# quadcopter.net
KiCad netlist of a schematic drawn in EAGLE
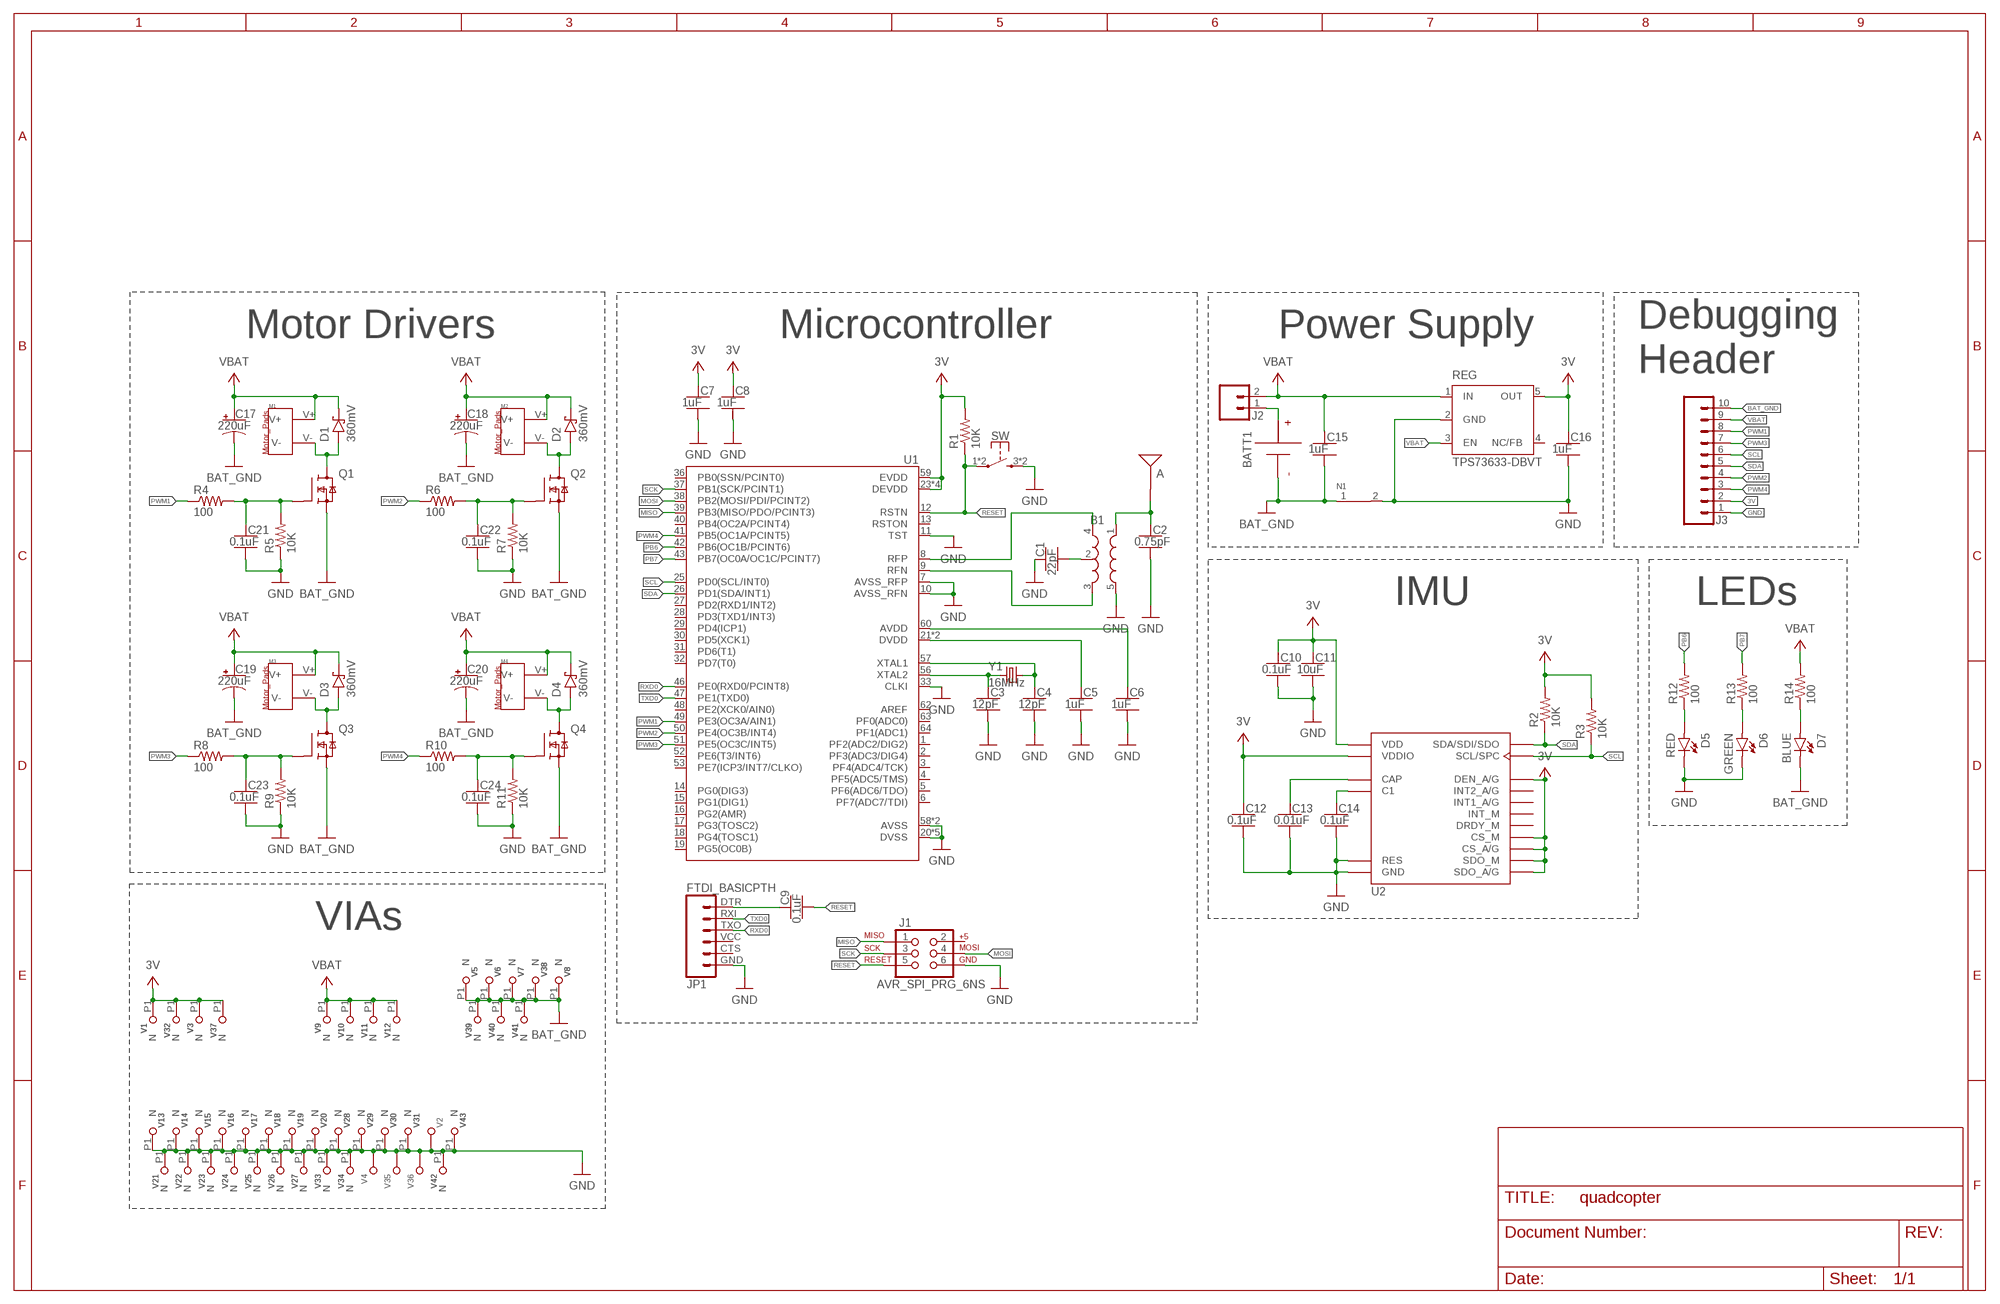
[diagram p0: schematic, sheet 1]

(export (version "E")
  (design (tool "Eeschema 10.0.6"))
  (components
    (comp (ref "A")
      (value "ANTENNA2SMD5")
      (footprint "eagle-import:ANTENNA-CHIP5")
      (fields (field (name "MFR") "Linx Technologies Inc.") (field (name "MPN") "ANT-2.45-CHP-T"))
      (libsource (lib "eagle-import") (part "ANTENNA2SMD5"))
    )
    (comp (ref "B1")
      (value "BALUN0805")
      (footprint "eagle-import:BALUN")
      (fields (field (name "MFR") "Wurth Electronics Inc") (field (name "MPN") "748421245"))
      (libsource (lib "eagle-import") (part "BALUN0805"))
    )
    (comp (ref "BATT1")
      (value "BATTERY")
      (footprint "eagle-import:BATTERY-TERMINALS")
      (libsource (lib "eagle-import") (part "BATTERY"))
    )
    (comp (ref "C1")
      (value "22pF")
      (footprint "eagle-import:CAPC2012X140_HS")
      (fields
        (field (name "MFR") "Murata Electronics North America")
        (field (name "MPN") "GRM21A5C2E220JW01D")
      )
      (libsource (lib "eagle-import") (part "CAPACITOR-NP_SMD-2012-0805_CERAMIC-22PF"))
    )
    (comp (ref "C2")
      (value "0.75pF")
      (footprint "eagle-import:CAPC2012X140_HS")
      (fields
        (field (name "MFR") "Murata Electronics North America")
        (field (name "MPN") "GQM2195C2AR75CB01D")
      )
      (libsource (lib "eagle-import") (part "CAPACITOR-NP_SMD-2012-0805_CERAMIC-0.75PF"))
    )
    (comp (ref "C3")
      (value "12pF")
      (footprint "eagle-import:CAPC2012X140_HS")
      (fields
        (field (name "MFR") "Murata Electronics North America")
        (field (name "MPN") "GRM21A5C2E120JW01D")
      )
      (libsource (lib "eagle-import") (part "CAPACITOR-NP_SMD-2012-0805_CERAMIC-12PF"))
    )
    (comp (ref "C4")
      (value "12pF")
      (footprint "eagle-import:CAPC2012X140_HS")
      (fields
        (field (name "MFR") "Murata Electronics North America")
        (field (name "MPN") "GRM21A5C2E120JW01D")
      )
      (libsource (lib "eagle-import") (part "CAPACITOR-NP_SMD-2012-0805_CERAMIC-12PF"))
    )
    (comp (ref "C5")
      (value "1uF")
      (footprint "eagle-import:CAPC2012X140_HS")
      (fields (field (name "MFR") "Taiyo Yuden") (field (name "MPN") "TMK212B7105KG-T"))
      (libsource (lib "eagle-import") (part "CAPACITOR-NP_SMD-2012-0805_CERAMIC-1UF"))
    )
    (comp (ref "C6")
      (value "1uF")
      (footprint "eagle-import:CAPC2012X140_HS")
      (fields (field (name "MFR") "Taiyo Yuden") (field (name "MPN") "TMK212B7105KG-T"))
      (libsource (lib "eagle-import") (part "CAPACITOR-NP_SMD-2012-0805_CERAMIC-1UF"))
    )
    (comp (ref "C7")
      (value "1uF")
      (footprint "eagle-import:CAPC2012X140_HS")
      (fields (field (name "MFR") "Taiyo Yuden") (field (name "MPN") "TMK212B7105KG-T"))
      (libsource (lib "eagle-import") (part "CAPACITOR-NP_SMD-2012-0805_CERAMIC-1UF"))
    )
    (comp (ref "C8")
      (value "1uF")
      (footprint "eagle-import:CAPC2012X140_HS")
      (fields (field (name "MFR") "Taiyo Yuden") (field (name "MPN") "TMK212B7105KG-T"))
      (libsource (lib "eagle-import") (part "CAPACITOR-NP_SMD-2012-0805_CERAMIC-1UF"))
    )
    (comp (ref "C9")
      (value "0.1uF")
      (footprint "eagle-import:CAPC2012X140_HS")
      (fields (field (name "MFR") "TDK") (field (name "MPN") "C2012X7R2A104K125AA"))
      (libsource (lib "eagle-import") (part "CAPACITOR-NP_SMD-2012-0805_CERAMIC-0.1UF"))
    )
    (comp (ref "C10")
      (value "0.1uF")
      (footprint "eagle-import:CAPC2012X140_HS")
      (fields (field (name "MFR") "TDK") (field (name "MPN") "C2012X7R2A104K125AA"))
      (libsource (lib "eagle-import") (part "CAPACITOR-NP_SMD-2012-0805_CERAMIC-0.1UF"))
    )
    (comp (ref "C11")
      (value "10uF")
      (footprint "eagle-import:CAPC2012X140_HS")
      (fields (field (name "MFR") "TDK Corporation") (field (name "MPN") "C2012X5R1E106M085AC"))
      (libsource (lib "eagle-import") (part "CAPACITOR-NP_SMD-2012-0805_CERAMIC-10UF"))
    )
    (comp (ref "C12")
      (value "0.1uF")
      (footprint "eagle-import:CAPC2012X140_HS")
      (fields (field (name "MFR") "TDK") (field (name "MPN") "C2012X7R2A104K125AA"))
      (libsource (lib "eagle-import") (part "CAPACITOR-NP_SMD-2012-0805_CERAMIC-0.1UF"))
    )
    (comp (ref "C13")
      (value "0.01uF")
      (footprint "eagle-import:CAPC2012X140_HS")
      (fields (field (name "MFR") "Knowles Syfer") (field (name "MPN") "0805J0500104KJT"))
      (libsource (lib "eagle-import") (part "CAPACITOR-NP_SMD-2012-0805_CERAMIC-0.01UF"))
    )
    (comp (ref "C14")
      (value "0.1uF")
      (footprint "eagle-import:CAPC2012X140_HS")
      (fields (field (name "MFR") "TDK") (field (name "MPN") "C2012X7R2A104K125AA"))
      (libsource (lib "eagle-import") (part "CAPACITOR-NP_SMD-2012-0805_CERAMIC-0.1UF"))
    )
    (comp (ref "C15")
      (value "1uF")
      (footprint "eagle-import:CAPC2012X140_HS")
      (fields (field (name "MFR") "Taiyo Yuden") (field (name "MPN") "TMK212B7105KG-T"))
      (libsource (lib "eagle-import") (part "CAPACITOR-NP_SMD-2012-0805_CERAMIC-1UF"))
    )
    (comp (ref "C16")
      (value "1uF")
      (footprint "eagle-import:CAPC2012X140_HS")
      (fields (field (name "MFR") "Taiyo Yuden") (field (name "MPN") "TMK212B7105KG-T"))
      (libsource (lib "eagle-import") (part "CAPACITOR-NP_SMD-2012-0805_CERAMIC-1UF"))
    )
    (comp (ref "C17")
      (value "220uF")
      (footprint "eagle-import:CAPMP7343X310_HS")
      (fields (field (name "MFR") "AVX Corporation") (field (name "MPN") "TAJD227K006RNJ"))
      (libsource (lib "eagle-import") (part "CAPACITOR-POL_SMD-7043-D_TANTALUM-220UF"))
    )
    (comp (ref "C18")
      (value "220uF")
      (footprint "eagle-import:CAPMP7343X310_HS")
      (fields (field (name "MFR") "AVX Corporation") (field (name "MPN") "TAJD227K006RNJ"))
      (libsource (lib "eagle-import") (part "CAPACITOR-POL_SMD-7043-D_TANTALUM-220UF"))
    )
    (comp (ref "C19")
      (value "220uF")
      (footprint "eagle-import:CAPMP7343X310_HS")
      (fields (field (name "MFR") "AVX Corporation") (field (name "MPN") "TAJD227K006RNJ"))
      (libsource (lib "eagle-import") (part "CAPACITOR-POL_SMD-7043-D_TANTALUM-220UF"))
    )
    (comp (ref "C20")
      (value "220uF")
      (footprint "eagle-import:CAPMP7343X310_HS")
      (fields (field (name "MFR") "AVX Corporation") (field (name "MPN") "TAJD227K006RNJ"))
      (libsource (lib "eagle-import") (part "CAPACITOR-POL_SMD-7043-D_TANTALUM-220UF"))
    )
    (comp (ref "C21")
      (value "0.1uF")
      (footprint "eagle-import:CAPC2012X140_HS")
      (fields (field (name "MFR") "TDK") (field (name "MPN") "C2012X7R2A104K125AA"))
      (libsource (lib "eagle-import") (part "CAPACITOR-NP_SMD-2012-0805_CERAMIC-0.1UF"))
    )
    (comp (ref "C22")
      (value "0.1uF")
      (footprint "eagle-import:CAPC2012X140_HS")
      (fields (field (name "MFR") "TDK") (field (name "MPN") "C2012X7R2A104K125AA"))
      (libsource (lib "eagle-import") (part "CAPACITOR-NP_SMD-2012-0805_CERAMIC-0.1UF"))
    )
    (comp (ref "C23")
      (value "0.1uF")
      (footprint "eagle-import:CAPC2012X140_HS")
      (fields (field (name "MFR") "TDK") (field (name "MPN") "C2012X7R2A104K125AA"))
      (libsource (lib "eagle-import") (part "CAPACITOR-NP_SMD-2012-0805_CERAMIC-0.1UF"))
    )
    (comp (ref "C24")
      (value "0.1uF")
      (footprint "eagle-import:CAPC2012X140_HS")
      (fields (field (name "MFR") "TDK") (field (name "MPN") "C2012X7R2A104K125AA"))
      (libsource (lib "eagle-import") (part "CAPACITOR-NP_SMD-2012-0805_CERAMIC-0.1UF"))
    )
    (comp (ref "D1")
      (value "360mV")
      (footprint "eagle-import:SOD3716X135_HS")
      (fields
        (field (name "MFR") "Toshiba Semiconductor and Storage")
        (field (name "MPN") "CRS08(TE85L,Q,M)")
      )
      (libsource (lib "eagle-import") (part "DIODE-SCHOTTKY_SMD-SOD123-360MV"))
    )
    (comp (ref "D2")
      (value "360mV")
      (footprint "eagle-import:SOD3716X135_HS")
      (fields
        (field (name "MFR") "Toshiba Semiconductor and Storage")
        (field (name "MPN") "CRS08(TE85L,Q,M)")
      )
      (libsource (lib "eagle-import") (part "DIODE-SCHOTTKY_SMD-SOD123-360MV"))
    )
    (comp (ref "D3")
      (value "360mV")
      (footprint "eagle-import:SOD3716X135_HS")
      (fields
        (field (name "MFR") "Toshiba Semiconductor and Storage")
        (field (name "MPN") "CRS08(TE85L,Q,M)")
      )
      (libsource (lib "eagle-import") (part "DIODE-SCHOTTKY_SMD-SOD123-360MV"))
    )
    (comp (ref "D4")
      (value "360mV")
      (footprint "eagle-import:SOD3716X135_HS")
      (fields
        (field (name "MFR") "Toshiba Semiconductor and Storage")
        (field (name "MPN") "CRS08(TE85L,Q,M)")
      )
      (libsource (lib "eagle-import") (part "DIODE-SCHOTTKY_SMD-SOD123-360MV"))
    )
    (comp (ref "D5")
      (value "RED")
      (footprint "eagle-import:LED_0805")
      (fields (field (name "MFR") "Lite-On Inc") (field (name "MPN") "LTST-C170KRKT"))
      (libsource (lib "eagle-import") (part "LED_RED"))
    )
    (comp (ref "D6")
      (value "GREEN")
      (footprint "eagle-import:LED_0805")
      (fields (field (name "MFR") "Lite-On Inc") (field (name "MPN") "LTST-C170TGKT"))
      (libsource (lib "eagle-import") (part "LED_GREEN"))
    )
    (comp (ref "D7")
      (value "BLUE")
      (footprint "eagle-import:LED_0805")
      (fields (field (name "MFR") "Lite-On Inc") (field (name "MPN") "LTST-C170TBKT"))
      (libsource (lib "eagle-import") (part "LED_BLUE"))
    )
    (comp (ref "J1")
      (value "AVR_SPI_PRG_6NS")
      (footprint "eagle-import:2X3-NS")
      (fields (field (name "MFR") "Amphenol FCI") (field (name "MPN") "67997-206HLF"))
      (libsource (lib "eagle-import") (part "AVR_SPI_PRG_6NS"))
    )
    (comp (ref "J2")
      (value "MALE_HEADER_2POS-2X1-0.1IN")
      (footprint "eagle-import:MALE_HEADER_2X1_0.1IN")
      (fields (field (name "MFR") "3M") (field (name "MPN") "961102-6404-AR"))
      (libsource (lib "eagle-import") (part "MALE_HEADER_2POS-2X1-0.1IN"))
    )
    (comp (ref "J3")
      (value "SIP-10_TH-254X10")
      (footprint "eagle-import:HDRV10W63P254_10X1_2540X254H838_HS")
      (fields (field (name "MFR") "Amphenol FCI") (field (name "MPN") "68000-110HLF"))
      (libsource (lib "eagle-import") (part "SIP-10_TH-254X10"))
    )
    (comp (ref "JP1")
      (value "FTDI_BASICPTH")
      (footprint "eagle-import:FTDI_BASIC")
      (fields (field (name "MFR") "Amphenol FCI") (field (name "MPN") "68016-406HLF"))
      (libsource (lib "eagle-import") (part "FTDI_BASICPTH"))
    )
    (comp (ref "M1")
      (value "MOTOR_PADS")
      (footprint "eagle-import:MOTOR_PADS")
      (fields (field (name "MFR") "NA"))
      (libsource (lib "eagle-import") (part "MOTOR_PADS"))
    )
    (comp (ref "M2")
      (value "MOTOR_PADS")
      (footprint "eagle-import:MOTOR_PADS")
      (fields (field (name "MFR") "NA"))
      (libsource (lib "eagle-import") (part "MOTOR_PADS"))
    )
    (comp (ref "M3")
      (value "MOTOR_PADS")
      (footprint "eagle-import:MOTOR_PADS")
      (fields (field (name "MFR") "NA"))
      (libsource (lib "eagle-import") (part "MOTOR_PADS"))
    )
    (comp (ref "M4")
      (value "MOTOR_PADS")
      (footprint "eagle-import:MOTOR_PADS")
      (fields (field (name "MFR") "NA"))
      (libsource (lib "eagle-import") (part "MOTOR_PADS"))
    )
    (comp (ref "N1")
      (value "NET_BRIDGE")
      (footprint "eagle-import:NET_BRIDGE")
      (libsource (lib "eagle-import") (part "NET_BRIDGE"))
    )
    (comp (ref "Q1")
      (value "MOSFET_SOT-23")
      (footprint "eagle-import:SI2302CDS_T1_E3")
      (fields (field (name "MFR") "Vishay Siliconix") (field (name "MPN") "SI2302CDS-T1-E3"))
      (libsource (lib "eagle-import") (part "MOSFET_SOT-23"))
    )
    (comp (ref "Q2")
      (value "MOSFET_SOT-23")
      (footprint "eagle-import:SI2302CDS_T1_E3")
      (fields (field (name "MFR") "Vishay Siliconix") (field (name "MPN") "SI2302CDS-T1-E3"))
      (libsource (lib "eagle-import") (part "MOSFET_SOT-23"))
    )
    (comp (ref "Q3")
      (value "MOSFET_SOT-23")
      (footprint "eagle-import:SI2302CDS_T1_E3")
      (fields (field (name "MFR") "Vishay Siliconix") (field (name "MPN") "SI2302CDS-T1-E3"))
      (libsource (lib "eagle-import") (part "MOSFET_SOT-23"))
    )
    (comp (ref "Q4")
      (value "MOSFET_SOT-23")
      (footprint "eagle-import:SI2302CDS_T1_E3")
      (fields (field (name "MFR") "Vishay Siliconix") (field (name "MPN") "SI2302CDS-T1-E3"))
      (libsource (lib "eagle-import") (part "MOSFET_SOT-23"))
    )
    (comp (ref "R1")
      (value "10K")
      (footprint "eagle-import:RESC2012X60_HS")
      (fields (field (name "MFR") "Yageo") (field (name "MPN") "RC0805JR-0710KL"))
      (libsource (lib "eagle-import") (part "RESISTOR_SMD-2012-0805-10K"))
    )
    (comp (ref "R2")
      (value "10K")
      (footprint "eagle-import:RESC2012X60_HS")
      (fields (field (name "MFR") "Yageo") (field (name "MPN") "RC0805JR-0710KL"))
      (libsource (lib "eagle-import") (part "RESISTOR_SMD-2012-0805-10K"))
    )
    (comp (ref "R3")
      (value "10K")
      (footprint "eagle-import:RESC2012X60_HS")
      (fields (field (name "MFR") "Yageo") (field (name "MPN") "RC0805JR-0710KL"))
      (libsource (lib "eagle-import") (part "RESISTOR_SMD-2012-0805-10K"))
    )
    (comp (ref "R4")
      (value "100")
      (footprint "eagle-import:RESC2012X60_HS")
      (fields (field (name "MFR") "Yageo") (field (name "MPN") "RC0805JR-07100RL"))
      (libsource (lib "eagle-import") (part "RESISTOR_SMD-2012-0805-100"))
    )
    (comp (ref "R5")
      (value "10K")
      (footprint "eagle-import:RESC2012X60_HS")
      (fields (field (name "MFR") "Yageo") (field (name "MPN") "RC0805JR-0710KL"))
      (libsource (lib "eagle-import") (part "RESISTOR_SMD-2012-0805-10K"))
    )
    (comp (ref "R6")
      (value "100")
      (footprint "eagle-import:RESC2012X60_HS")
      (fields (field (name "MFR") "Yageo") (field (name "MPN") "RC0805JR-07100RL"))
      (libsource (lib "eagle-import") (part "RESISTOR_SMD-2012-0805-100"))
    )
    (comp (ref "R7")
      (value "10K")
      (footprint "eagle-import:RESC2012X60_HS")
      (fields (field (name "MFR") "Yageo") (field (name "MPN") "RC0805JR-0710KL"))
      (libsource (lib "eagle-import") (part "RESISTOR_SMD-2012-0805-10K"))
    )
    (comp (ref "R8")
      (value "100")
      (footprint "eagle-import:RESC2012X60_HS")
      (fields (field (name "MFR") "Yageo") (field (name "MPN") "RC0805JR-07100RL"))
      (libsource (lib "eagle-import") (part "RESISTOR_SMD-2012-0805-100"))
    )
    (comp (ref "R9")
      (value "10K")
      (footprint "eagle-import:RESC2012X60_HS")
      (fields (field (name "MFR") "Yageo") (field (name "MPN") "RC0805JR-0710KL"))
      (libsource (lib "eagle-import") (part "RESISTOR_SMD-2012-0805-10K"))
    )
    (comp (ref "R10")
      (value "100")
      (footprint "eagle-import:RESC2012X60_HS")
      (fields (field (name "MFR") "Yageo") (field (name "MPN") "RC0805JR-07100RL"))
      (libsource (lib "eagle-import") (part "RESISTOR_SMD-2012-0805-100"))
    )
    (comp (ref "R11")
      (value "10K")
      (footprint "eagle-import:RESC2012X60_HS")
      (fields (field (name "MFR") "Yageo") (field (name "MPN") "RC0805JR-0710KL"))
      (libsource (lib "eagle-import") (part "RESISTOR_SMD-2012-0805-10K"))
    )
    (comp (ref "R12")
      (value "100")
      (footprint "eagle-import:RESC2012X60_HS")
      (fields (field (name "MFR") "Yageo") (field (name "MPN") "RC0805JR-07100RL"))
      (libsource (lib "eagle-import") (part "RESISTOR_SMD-2012-0805-100"))
    )
    (comp (ref "R13")
      (value "100")
      (footprint "eagle-import:RESC2012X60_HS")
      (fields (field (name "MFR") "Yageo") (field (name "MPN") "RC0805JR-07100RL"))
      (libsource (lib "eagle-import") (part "RESISTOR_SMD-2012-0805-100"))
    )
    (comp (ref "R14")
      (value "100")
      (footprint "eagle-import:RESC2012X60_HS")
      (fields (field (name "MFR") "Yageo") (field (name "MPN") "RC0805JR-07100RL"))
      (libsource (lib "eagle-import") (part "RESISTOR_SMD-2012-0805-100"))
    )
    (comp (ref "REG")
      (value "TPS73633-DBVT")
      (footprint "eagle-import:SOT23-DBV")
      (fields (field (name "MFR") "Texas Instruments") (field (name "MPN") "LP3985IM5X-3.0/NOPB"))
      (libsource (lib "eagle-import") (part "TPS73633-DBVT"))
    )
    (comp (ref "SW")
      (value "PUSHBUTTON_SMD-VERTICAL-1")
      (footprint "eagle-import:TE_FSM8JSMA_HS")
      (fields (field (name "MFR") "TE Connectivity Alcoswitch Switches") (field (name "MPN") "FSM4JSMA"))
      (libsource (lib "eagle-import") (part "PUSHBUTTON_SMD-VERTICAL-1"))
    )
    (comp (ref "U1")
      (value "ATMEGA128RFA1")
      (footprint "eagle-import:QFN-64")
      (fields (field (name "MFR") "Atmel") (field (name "MPN") "ATMEGA128RFA1-ZUR00"))
      (libsource (lib "eagle-import") (part "ATMEGA128RFA1"))
    )
    (comp (ref "U2")
      (value "IMU_LSM9DS1TR")
      (footprint "eagle-import:LSM9DS1TR")
      (fields (field (name "MFR") "STMicroelectronics") (field (name "MPN") "LSM9DS1TR"))
      (libsource (lib "eagle-import") (part "IMU_LSM9DS1TR"))
    )
    (comp (ref "V1")
      (value "LOCKED-VIA-0.254")
      (footprint "eagle-import:VIA-0.254MM")
      (libsource (lib "eagle-import") (part "LOCKED-VIA-0.254"))
    )
    (comp (ref "V2")
      (value "VIA_0.454")
      (footprint "eagle-import:VIA_0.454")
      (libsource (lib "eagle-import") (part "VIA_0.454"))
    )
    (comp (ref "V3")
      (value "LOCKED-VIA-0.254")
      (footprint "eagle-import:VIA-0.254MM")
      (libsource (lib "eagle-import") (part "LOCKED-VIA-0.254"))
    )
    (comp (ref "V4")
      (value "VIA_0.454")
      (footprint "eagle-import:VIA_0.454")
      (libsource (lib "eagle-import") (part "VIA_0.454"))
    )
    (comp (ref "V5")
      (value "LOCKED-VIA-0.254")
      (footprint "eagle-import:VIA-0.254MM")
      (libsource (lib "eagle-import") (part "LOCKED-VIA-0.254"))
    )
    (comp (ref "V6")
      (value "LOCKED-VIA-0.254")
      (footprint "eagle-import:VIA-0.254MM")
      (libsource (lib "eagle-import") (part "LOCKED-VIA-0.254"))
    )
    (comp (ref "V7")
      (value "LOCKED-VIA-0.254")
      (footprint "eagle-import:VIA-0.254MM")
      (libsource (lib "eagle-import") (part "LOCKED-VIA-0.254"))
    )
    (comp (ref "V8")
      (value "LOCKED-VIA-0.254")
      (footprint "eagle-import:VIA-0.254MM")
      (libsource (lib "eagle-import") (part "LOCKED-VIA-0.254"))
    )
    (comp (ref "V9")
      (value "LOCKED-VIA-0.254")
      (footprint "eagle-import:VIA-0.254MM")
      (libsource (lib "eagle-import") (part "LOCKED-VIA-0.254"))
    )
    (comp (ref "V10")
      (value "LOCKED-VIA-0.254")
      (footprint "eagle-import:VIA-0.254MM")
      (libsource (lib "eagle-import") (part "LOCKED-VIA-0.254"))
    )
    (comp (ref "V11")
      (value "LOCKED-VIA-0.254")
      (footprint "eagle-import:VIA-0.254MM")
      (libsource (lib "eagle-import") (part "LOCKED-VIA-0.254"))
    )
    (comp (ref "V12")
      (value "LOCKED-VIA-0.254")
      (footprint "eagle-import:VIA-0.254MM")
      (libsource (lib "eagle-import") (part "LOCKED-VIA-0.254"))
    )
    (comp (ref "V13")
      (value "LOCKED-VIA-0.254")
      (footprint "eagle-import:VIA-0.254MM")
      (libsource (lib "eagle-import") (part "LOCKED-VIA-0.254"))
    )
    (comp (ref "V14")
      (value "LOCKED-VIA-0.254")
      (footprint "eagle-import:VIA-0.254MM")
      (libsource (lib "eagle-import") (part "LOCKED-VIA-0.254"))
    )
    (comp (ref "V15")
      (value "LOCKED-VIA-0.254")
      (footprint "eagle-import:VIA-0.254MM")
      (libsource (lib "eagle-import") (part "LOCKED-VIA-0.254"))
    )
    (comp (ref "V16")
      (value "LOCKED-VIA-0.254")
      (footprint "eagle-import:VIA-0.254MM")
      (libsource (lib "eagle-import") (part "LOCKED-VIA-0.254"))
    )
    (comp (ref "V17")
      (value "LOCKED-VIA-0.254")
      (footprint "eagle-import:VIA-0.254MM")
      (libsource (lib "eagle-import") (part "LOCKED-VIA-0.254"))
    )
    (comp (ref "V18")
      (value "LOCKED-VIA-0.254")
      (footprint "eagle-import:VIA-0.254MM")
      (libsource (lib "eagle-import") (part "LOCKED-VIA-0.254"))
    )
    (comp (ref "V19")
      (value "LOCKED-VIA-0.254")
      (footprint "eagle-import:VIA-0.254MM")
      (libsource (lib "eagle-import") (part "LOCKED-VIA-0.254"))
    )
    (comp (ref "V20")
      (value "LOCKED-VIA-0.254")
      (footprint "eagle-import:VIA-0.254MM")
      (libsource (lib "eagle-import") (part "LOCKED-VIA-0.254"))
    )
    (comp (ref "V21")
      (value "LOCKED-VIA-0.254")
      (footprint "eagle-import:VIA-0.254MM")
      (libsource (lib "eagle-import") (part "LOCKED-VIA-0.254"))
    )
    (comp (ref "V22")
      (value "LOCKED-VIA-0.254")
      (footprint "eagle-import:VIA-0.254MM")
      (libsource (lib "eagle-import") (part "LOCKED-VIA-0.254"))
    )
    (comp (ref "V23")
      (value "LOCKED-VIA-0.254")
      (footprint "eagle-import:VIA-0.254MM")
      (libsource (lib "eagle-import") (part "LOCKED-VIA-0.254"))
    )
    (comp (ref "V24")
      (value "LOCKED-VIA-0.254")
      (footprint "eagle-import:VIA-0.254MM")
      (libsource (lib "eagle-import") (part "LOCKED-VIA-0.254"))
    )
    (comp (ref "V25")
      (value "LOCKED-VIA-0.254")
      (footprint "eagle-import:VIA-0.254MM")
      (libsource (lib "eagle-import") (part "LOCKED-VIA-0.254"))
    )
    (comp (ref "V26")
      (value "LOCKED-VIA-0.254")
      (footprint "eagle-import:VIA-0.254MM")
      (libsource (lib "eagle-import") (part "LOCKED-VIA-0.254"))
    )
    (comp (ref "V27")
      (value "LOCKED-VIA-0.254")
      (footprint "eagle-import:VIA-0.254MM")
      (libsource (lib "eagle-import") (part "LOCKED-VIA-0.254"))
    )
    (comp (ref "V28")
      (value "LOCKED-VIA-0.254")
      (footprint "eagle-import:VIA-0.254MM")
      (libsource (lib "eagle-import") (part "LOCKED-VIA-0.254"))
    )
    (comp (ref "V29")
      (value "LOCKED-VIA-0.254")
      (footprint "eagle-import:VIA-0.254MM")
      (libsource (lib "eagle-import") (part "LOCKED-VIA-0.254"))
    )
    (comp (ref "V30")
      (value "LOCKED-VIA-0.254")
      (footprint "eagle-import:VIA-0.254MM")
      (libsource (lib "eagle-import") (part "LOCKED-VIA-0.254"))
    )
    (comp (ref "V31")
      (value "LOCKED-VIA-0.254")
      (footprint "eagle-import:VIA-0.254MM")
      (libsource (lib "eagle-import") (part "LOCKED-VIA-0.254"))
    )
    (comp (ref "V32")
      (value "LOCKED-VIA-0.254")
      (footprint "eagle-import:VIA-0.254MM")
      (libsource (lib "eagle-import") (part "LOCKED-VIA-0.254"))
    )
    (comp (ref "V33")
      (value "LOCKED-VIA-0.254")
      (footprint "eagle-import:VIA-0.254MM")
      (libsource (lib "eagle-import") (part "LOCKED-VIA-0.254"))
    )
    (comp (ref "V34")
      (value "LOCKED-VIA-0.254")
      (footprint "eagle-import:VIA-0.254MM")
      (libsource (lib "eagle-import") (part "LOCKED-VIA-0.254"))
    )
    (comp (ref "V35")
      (value "VIA_0.454")
      (footprint "eagle-import:VIA_0.454")
      (libsource (lib "eagle-import") (part "VIA_0.454"))
    )
    (comp (ref "V36")
      (value "VIA_0.454")
      (footprint "eagle-import:VIA_0.454")
      (libsource (lib "eagle-import") (part "VIA_0.454"))
    )
    (comp (ref "V37")
      (value "LOCKED-VIA-0.254")
      (footprint "eagle-import:VIA-0.254MM")
      (libsource (lib "eagle-import") (part "LOCKED-VIA-0.254"))
    )
    (comp (ref "V38")
      (value "LOCKED-VIA-0.254")
      (footprint "eagle-import:VIA-0.254MM")
      (libsource (lib "eagle-import") (part "LOCKED-VIA-0.254"))
    )
    (comp (ref "V39")
      (value "LOCKED-VIA-0.254")
      (footprint "eagle-import:VIA-0.254MM")
      (libsource (lib "eagle-import") (part "LOCKED-VIA-0.254"))
    )
    (comp (ref "V40")
      (value "LOCKED-VIA-0.254")
      (footprint "eagle-import:VIA-0.254MM")
      (libsource (lib "eagle-import") (part "LOCKED-VIA-0.254"))
    )
    (comp (ref "V41")
      (value "LOCKED-VIA-0.254")
      (footprint "eagle-import:VIA-0.254MM")
      (libsource (lib "eagle-import") (part "LOCKED-VIA-0.254"))
    )
    (comp (ref "V42")
      (value "LOCKED-VIA-0.254")
      (footprint "eagle-import:VIA-0.254MM")
      (libsource (lib "eagle-import") (part "LOCKED-VIA-0.254"))
    )
    (comp (ref "V43")
      (value "LOCKED-VIA-0.254")
      (footprint "eagle-import:VIA-0.254MM")
      (libsource (lib "eagle-import") (part "LOCKED-VIA-0.254"))
    )
    (comp (ref "Y1")
      (value "16MHz")
      (footprint "eagle-import:CRYSTAL-SMD-5X3")
      (fields (field (name "MFR") "Abracon LLC") (field (name "MPN") "ABM3B-16.000MHZ-B2-T"))
      (libsource (lib "eagle-import") (part "CRYSTAL5X3"))
    )
  )
  (nets
    (net (code "1") (name "3V") (class "Default")
      (node (ref "C10") (pin "1") (pinfunction "1_1") (pintype "passive"))
      (node (ref "C11") (pin "1") (pinfunction "1_1") (pintype "passive"))
      (node (ref "C12") (pin "1") (pinfunction "1_1") (pintype "passive"))
      (node (ref "C16") (pin "1") (pinfunction "1_1") (pintype "passive"))
      (node (ref "C7") (pin "1") (pinfunction "1_1") (pintype "passive"))
      (node (ref "C8") (pin "1") (pinfunction "1_1") (pintype "passive"))
      (node (ref "J3") (pin "2") (pinfunction "2_2") (pintype "passive"))
      (node (ref "R1") (pin "2") (pinfunction "2_2") (pintype "passive"))
      (node (ref "R2") (pin "2") (pinfunction "2_2") (pintype "passive"))
      (node (ref "R3") (pin "2") (pinfunction "2_2") (pintype "passive"))
      (node (ref "REG") (pin "5") (pinfunction "OUT_5") (pintype "passive"))
      (node (ref "U1") (pin "23") (pinfunction "DEVDD_23") (pintype "bidirectional"))
      (node (ref "U1") (pin "34") (pinfunction "DEVDD_34") (pintype "bidirectional"))
      (node (ref "U1") (pin "44") (pinfunction "DEVDD_44") (pintype "bidirectional"))
      (node (ref "U1") (pin "54") (pinfunction "DEVDD_54") (pintype "bidirectional"))
      (node (ref "U1") (pin "59") (pinfunction "EVDD_59") (pintype "bidirectional"))
      (node (ref "U2") (pin "CS_A/G") (pinfunction "CS_A/G_CS_A/G") (pintype "bidirectional"))
      (node (ref "U2") (pin "CS_M") (pinfunction "CS_M_CS_M") (pintype "bidirectional"))
      (node (ref "U2") (pin "DEN_A/G") (pinfunction "DEN_A/G_DEN_A/G") (pintype "bidirectional"))
      (node (ref "U2") (pin "SDO_A/G") (pinfunction "SDO_A/G_SDO_A/G") (pintype "bidirectional"))
      (node (ref "U2") (pin "SDO_M") (pinfunction "SDO_M_SDO_M") (pintype "bidirectional"))
      (node (ref "U2") (pin "VDD") (pinfunction "VDD_VDD") (pintype "bidirectional"))
      (node (ref "U2") (pin "VDDIO") (pinfunction "VDDIO_VDDIO") (pintype "bidirectional"))
      (node (ref "U2") (pin "VDDIO_3") (pinfunction "VDDIO_VDDIO_3") (pintype "bidirectional"))
      (node (ref "U2") (pin "VDD_23") (pinfunction "VDD_VDD_23") (pintype "bidirectional"))
      (node (ref "V1") (pin "P1") (pinfunction "N_P1") (pintype "bidirectional"))
      (node (ref "V3") (pin "P1") (pinfunction "N_P1") (pintype "bidirectional"))
      (node (ref "V32") (pin "P1") (pinfunction "N_P1") (pintype "bidirectional"))
      (node (ref "V37") (pin "P1") (pinfunction "N_P1") (pintype "bidirectional"))
    )
    (net (code "2") (name "BAT_GND") (class "Default")
      (node (ref "BATT1") (pin "-") (pinfunction "N_-") (pintype "bidirectional"))
      (node (ref "C15") (pin "2") (pinfunction "2_2") (pintype "passive"))
      (node (ref "C17") (pin "2") (pinfunction "-_2") (pintype "passive"))
      (node (ref "C18") (pin "2") (pinfunction "-_2") (pintype "passive"))
      (node (ref "C19") (pin "2") (pinfunction "-_2") (pintype "passive"))
      (node (ref "C20") (pin "2") (pinfunction "-_2") (pintype "passive"))
      (node (ref "D7") (pin "C") (pinfunction "C_C") (pintype "bidirectional"))
      (node (ref "J3") (pin "10") (pinfunction "10_10") (pintype "passive"))
      (node (ref "N1") (pin "1") (pinfunction "1_1") (pintype "bidirectional"))
      (node (ref "Q1") (pin "S") (pinfunction "S_S") (pintype "passive"))
      (node (ref "Q2") (pin "S") (pinfunction "S_S") (pintype "passive"))
      (node (ref "Q3") (pin "S") (pinfunction "S_S") (pintype "passive"))
      (node (ref "Q4") (pin "S") (pinfunction "S_S") (pintype "passive"))
      (node (ref "V38") (pin "P1") (pinfunction "N_P1") (pintype "bidirectional"))
      (node (ref "V39") (pin "P1") (pinfunction "N_P1") (pintype "bidirectional"))
      (node (ref "V40") (pin "P1") (pinfunction "N_P1") (pintype "bidirectional"))
      (node (ref "V41") (pin "P1") (pinfunction "N_P1") (pintype "bidirectional"))
      (node (ref "V5") (pin "P1") (pinfunction "N_P1") (pintype "bidirectional"))
      (node (ref "V6") (pin "P1") (pinfunction "N_P1") (pintype "bidirectional"))
      (node (ref "V7") (pin "P1") (pinfunction "N_P1") (pintype "bidirectional"))
      (node (ref "V8") (pin "P1") (pinfunction "N_P1") (pintype "bidirectional"))
    )
    (net (code "3") (name "GND") (class "Default")
      (node (ref "B1") (pin "5") (pinfunction "GND_5") (pintype "bidirectional"))
      (node (ref "C1") (pin "1") (pinfunction "1_1") (pintype "passive"))
      (node (ref "C10") (pin "2") (pinfunction "2_2") (pintype "passive"))
      (node (ref "C11") (pin "2") (pinfunction "2_2") (pintype "passive"))
      (node (ref "C12") (pin "2") (pinfunction "2_2") (pintype "passive"))
      (node (ref "C13") (pin "2") (pinfunction "2_2") (pintype "passive"))
      (node (ref "C14") (pin "2") (pinfunction "2_2") (pintype "passive"))
      (node (ref "C16") (pin "2") (pinfunction "2_2") (pintype "passive"))
      (node (ref "C2") (pin "2") (pinfunction "2_2") (pintype "passive"))
      (node (ref "C21") (pin "2") (pinfunction "2_2") (pintype "passive"))
      (node (ref "C22") (pin "2") (pinfunction "2_2") (pintype "passive"))
      (node (ref "C23") (pin "2") (pinfunction "2_2") (pintype "passive"))
      (node (ref "C24") (pin "2") (pinfunction "2_2") (pintype "passive"))
      (node (ref "C3") (pin "2") (pinfunction "2_2") (pintype "passive"))
      (node (ref "C4") (pin "2") (pinfunction "2_2") (pintype "passive"))
      (node (ref "C5") (pin "2") (pinfunction "2_2") (pintype "passive"))
      (node (ref "C6") (pin "2") (pinfunction "2_2") (pintype "passive"))
      (node (ref "C7") (pin "2") (pinfunction "2_2") (pintype "passive"))
      (node (ref "C8") (pin "2") (pinfunction "2_2") (pintype "passive"))
      (node (ref "D5") (pin "C") (pinfunction "C_C") (pintype "bidirectional"))
      (node (ref "D6") (pin "C") (pinfunction "C_C") (pintype "bidirectional"))
      (node (ref "J1") (pin "6") (pinfunction "6_6") (pintype "passive"))
      (node (ref "J3") (pin "1") (pinfunction "1_1") (pintype "passive"))
      (node (ref "JP1") (pin "GND") (pinfunction "6_GND") (pintype "passive"))
      (node (ref "N1") (pin "2") (pinfunction "2_2") (pintype "bidirectional"))
      (node (ref "R11") (pin "1") (pinfunction "1_1") (pintype "passive"))
      (node (ref "R5") (pin "1") (pinfunction "1_1") (pintype "passive"))
      (node (ref "R7") (pin "1") (pinfunction "1_1") (pintype "passive"))
      (node (ref "R9") (pin "1") (pinfunction "1_1") (pintype "passive"))
      (node (ref "REG") (pin "2") (pinfunction "GND_2") (pintype "input"))
      (node (ref "SW") (pin "3") (pinfunction "2_3") (pintype "passive"))
      (node (ref "SW") (pin "4") (pinfunction "2_4") (pintype "passive"))
      (node (ref "U1") (pin "10") (pinfunction "AVSS_RFN_10") (pintype "bidirectional"))
      (node (ref "U1") (pin "11") (pinfunction "TST_11") (pintype "bidirectional"))
      (node (ref "U1") (pin "20") (pinfunction "DVSS_20") (pintype "bidirectional"))
      (node (ref "U1") (pin "24") (pinfunction "DVSS_24") (pintype "bidirectional"))
      (node (ref "U1") (pin "33") (pinfunction "CLKI_33") (pintype "bidirectional"))
      (node (ref "U1") (pin "35") (pinfunction "DVSS_35") (pintype "bidirectional"))
      (node (ref "U1") (pin "45") (pinfunction "DVSS_45") (pintype "bidirectional"))
      (node (ref "U1") (pin "55") (pinfunction "DVSS_55") (pintype "bidirectional"))
      (node (ref "U1") (pin "58") (pinfunction "AVSS_58") (pintype "bidirectional"))
      (node (ref "U1") (pin "61") (pinfunction "AVSS_61") (pintype "bidirectional"))
      (node (ref "U1") (pin "7") (pinfunction "AVSS_RFP_7") (pintype "bidirectional"))
      (node (ref "U2") (pin "GND") (pinfunction "GND_GND") (pintype "bidirectional"))
      (node (ref "U2") (pin "GND_20") (pinfunction "GND_GND_20") (pintype "bidirectional"))
      (node (ref "U2") (pin "RES") (pinfunction "RES_RES") (pintype "bidirectional"))
      (node (ref "U2") (pin "RES_15") (pinfunction "RES_RES_15") (pintype "bidirectional"))
      (node (ref "U2") (pin "RES_16") (pinfunction "RES_RES_16") (pintype "bidirectional"))
      (node (ref "U2") (pin "RES_17") (pinfunction "RES_RES_17") (pintype "bidirectional"))
      (node (ref "U2") (pin "RES_18") (pinfunction "RES_RES_18") (pintype "bidirectional"))
      (node (ref "V13") (pin "P1") (pinfunction "N_P1") (pintype "bidirectional"))
      (node (ref "V14") (pin "P1") (pinfunction "N_P1") (pintype "bidirectional"))
      (node (ref "V15") (pin "P1") (pinfunction "N_P1") (pintype "bidirectional"))
      (node (ref "V16") (pin "P1") (pinfunction "N_P1") (pintype "bidirectional"))
      (node (ref "V17") (pin "P1") (pinfunction "N_P1") (pintype "bidirectional"))
      (node (ref "V18") (pin "P1") (pinfunction "N_P1") (pintype "bidirectional"))
      (node (ref "V19") (pin "P1") (pinfunction "N_P1") (pintype "bidirectional"))
      (node (ref "V2") (pin "VIA") (pinfunction "VIA_VIA") (pintype "bidirectional"))
      (node (ref "V20") (pin "P1") (pinfunction "N_P1") (pintype "bidirectional"))
      (node (ref "V21") (pin "P1") (pinfunction "N_P1") (pintype "bidirectional"))
      (node (ref "V22") (pin "P1") (pinfunction "N_P1") (pintype "bidirectional"))
      (node (ref "V23") (pin "P1") (pinfunction "N_P1") (pintype "bidirectional"))
      (node (ref "V24") (pin "P1") (pinfunction "N_P1") (pintype "bidirectional"))
      (node (ref "V25") (pin "P1") (pinfunction "N_P1") (pintype "bidirectional"))
      (node (ref "V26") (pin "P1") (pinfunction "N_P1") (pintype "bidirectional"))
      (node (ref "V27") (pin "P1") (pinfunction "N_P1") (pintype "bidirectional"))
      (node (ref "V28") (pin "P1") (pinfunction "N_P1") (pintype "bidirectional"))
      (node (ref "V29") (pin "P1") (pinfunction "N_P1") (pintype "bidirectional"))
      (node (ref "V30") (pin "P1") (pinfunction "N_P1") (pintype "bidirectional"))
      (node (ref "V31") (pin "P1") (pinfunction "N_P1") (pintype "bidirectional"))
      (node (ref "V33") (pin "P1") (pinfunction "N_P1") (pintype "bidirectional"))
      (node (ref "V34") (pin "P1") (pinfunction "N_P1") (pintype "bidirectional"))
      (node (ref "V35") (pin "VIA") (pinfunction "VIA_VIA") (pintype "bidirectional"))
      (node (ref "V36") (pin "VIA") (pinfunction "VIA_VIA") (pintype "bidirectional"))
      (node (ref "V4") (pin "VIA") (pinfunction "VIA_VIA") (pintype "bidirectional"))
      (node (ref "V42") (pin "P1") (pinfunction "N_P1") (pintype "bidirectional"))
      (node (ref "V43") (pin "P1") (pinfunction "N_P1") (pintype "bidirectional"))
    )
    (net (code "4") (name "MISO") (class "Default")
      (node (ref "J1") (pin "1") (pinfunction "1_1") (pintype "passive"))
      (node (ref "U1") (pin "39") (pinfunction "PB3(MISO/PDO/PCINT3)_39") (pintype "bidirectional"))
    )
    (net (code "5") (name "MOSI") (class "Default")
      (node (ref "J1") (pin "4") (pinfunction "4_4") (pintype "passive"))
      (node (ref "U1") (pin "38") (pinfunction "PB2(MOSI/PDI/PCINT2)_38") (pintype "bidirectional"))
    )
    (net (code "6") (name "Net-(A-SIGNAL)") (class "Default")
      (node (ref "A") (pin "FEED") (pinfunction "SIGNAL_FEED") (pintype "bidirectional"))
      (node (ref "B1") (pin "1") (pinfunction "IN_1") (pintype "bidirectional"))
      (node (ref "C2") (pin "1") (pinfunction "1_1") (pintype "passive"))
    )
    (net (code "7") (name "Net-(B1-GND-Pad2)") (class "Default")
      (node (ref "B1") (pin "2") (pinfunction "GND_2") (pintype "bidirectional"))
      (node (ref "C1") (pin "2") (pinfunction "2_2") (pintype "passive"))
    )
    (net (code "8") (name "Net-(B1-OUT1)") (class "Default")
      (node (ref "B1") (pin "4") (pinfunction "OUT1_4") (pintype "bidirectional"))
      (node (ref "U1") (pin "8") (pinfunction "RFP_8") (pintype "bidirectional"))
    )
    (net (code "9") (name "Net-(B1-OUT2)") (class "Default")
      (node (ref "B1") (pin "3") (pinfunction "OUT2_3") (pintype "bidirectional"))
      (node (ref "U1") (pin "9") (pinfunction "RFN_9") (pintype "bidirectional"))
    )
    (net (code "10") (name "Net-(BATT1-P)") (class "Default")
      (node (ref "BATT1") (pin "+") (pinfunction "P_+") (pintype "bidirectional"))
      (node (ref "J2") (pin "1") (pinfunction "1_1") (pintype "passive"))
    )
    (net (code "11") (name "Net-(C5-Pad1)") (class "Default")
      (node (ref "C5") (pin "1") (pinfunction "1_1") (pintype "passive"))
      (node (ref "U1") (pin "21") (pinfunction "DVDD_21") (pintype "bidirectional"))
      (node (ref "U1") (pin "22") (pinfunction "DVDD_22") (pintype "bidirectional"))
    )
    (net (code "12") (name "Net-(C13-Pad1)") (class "Default")
      (node (ref "C13") (pin "1") (pinfunction "1_1") (pintype "passive"))
      (node (ref "U2") (pin "CAP") (pinfunction "CAP_CAP") (pintype "bidirectional"))
    )
    (net (code "13") (name "Net-(C14-Pad1)") (class "Default")
      (node (ref "C14") (pin "1") (pinfunction "1_1") (pintype "passive"))
      (node (ref "U2") (pin "C1") (pinfunction "C1_C1") (pintype "bidirectional"))
    )
    (net (code "14") (name "Net-(C21-Pad1)") (class "Default")
      (node (ref "C21") (pin "1") (pinfunction "1_1") (pintype "passive"))
      (node (ref "Q1") (pin "G") (pinfunction "G_G") (pintype "passive"))
      (node (ref "R4") (pin "2") (pinfunction "2_2") (pintype "passive"))
      (node (ref "R5") (pin "2") (pinfunction "2_2") (pintype "passive"))
    )
    (net (code "15") (name "Net-(C22-Pad1)") (class "Default")
      (node (ref "C22") (pin "1") (pinfunction "1_1") (pintype "passive"))
      (node (ref "Q2") (pin "G") (pinfunction "G_G") (pintype "passive"))
      (node (ref "R6") (pin "2") (pinfunction "2_2") (pintype "passive"))
      (node (ref "R7") (pin "2") (pinfunction "2_2") (pintype "passive"))
    )
    (net (code "16") (name "Net-(C23-Pad1)") (class "Default")
      (node (ref "C23") (pin "1") (pinfunction "1_1") (pintype "passive"))
      (node (ref "Q3") (pin "G") (pinfunction "G_G") (pintype "passive"))
      (node (ref "R8") (pin "2") (pinfunction "2_2") (pintype "passive"))
      (node (ref "R9") (pin "2") (pinfunction "2_2") (pintype "passive"))
    )
    (net (code "17") (name "Net-(C24-Pad1)") (class "Default")
      (node (ref "C24") (pin "1") (pinfunction "1_1") (pintype "passive"))
      (node (ref "Q4") (pin "G") (pinfunction "G_G") (pintype "passive"))
      (node (ref "R10") (pin "2") (pinfunction "2_2") (pintype "passive"))
      (node (ref "R11") (pin "2") (pinfunction "2_2") (pintype "passive"))
    )
    (net (code "18") (name "Net-(D1-PadA)") (class "Default")
      (node (ref "D1") (pin "A") (pinfunction "A_A") (pintype "passive"))
      (node (ref "M1") (pin "V-") (pinfunction "V-_V-") (pintype "bidirectional"))
      (node (ref "Q1") (pin "D") (pinfunction "D_D") (pintype "passive"))
    )
    (net (code "19") (name "Net-(D2-PadA)") (class "Default")
      (node (ref "D2") (pin "A") (pinfunction "A_A") (pintype "passive"))
      (node (ref "M2") (pin "V-") (pinfunction "V-_V-") (pintype "bidirectional"))
      (node (ref "Q2") (pin "D") (pinfunction "D_D") (pintype "passive"))
    )
    (net (code "20") (name "Net-(D3-PadA)") (class "Default")
      (node (ref "D3") (pin "A") (pinfunction "A_A") (pintype "passive"))
      (node (ref "M3") (pin "V-") (pinfunction "V-_V-") (pintype "bidirectional"))
      (node (ref "Q3") (pin "D") (pinfunction "D_D") (pintype "passive"))
    )
    (net (code "21") (name "Net-(D4-PadA)") (class "Default")
      (node (ref "D4") (pin "A") (pinfunction "A_A") (pintype "passive"))
      (node (ref "M4") (pin "V-") (pinfunction "V-_V-") (pintype "bidirectional"))
      (node (ref "Q4") (pin "D") (pinfunction "D_D") (pintype "passive"))
    )
    (net (code "22") (name "Net-(D5-PadA)") (class "Default")
      (node (ref "D5") (pin "A") (pinfunction "A_A") (pintype "bidirectional"))
      (node (ref "R12") (pin "1") (pinfunction "1_1") (pintype "passive"))
    )
    (net (code "23") (name "Net-(D6-PadA)") (class "Default")
      (node (ref "D6") (pin "A") (pinfunction "A_A") (pintype "bidirectional"))
      (node (ref "R13") (pin "1") (pinfunction "1_1") (pintype "passive"))
    )
    (net (code "24") (name "Net-(D7-PadA)") (class "Default")
      (node (ref "D7") (pin "A") (pinfunction "A_A") (pintype "bidirectional"))
      (node (ref "R14") (pin "1") (pinfunction "1_1") (pintype "passive"))
    )
    (net (code "25") (name "Net-(JP1-1)") (class "Default")
      (node (ref "C9") (pin "1") (pinfunction "1_1") (pintype "passive"))
      (node (ref "JP1") (pin "DTR") (pinfunction "1_DTR") (pintype "passive"))
    )
    (net (code "26") (name "Net-(U1-AVDD)") (class "Default")
      (node (ref "C6") (pin "1") (pinfunction "1_1") (pintype "passive"))
      (node (ref "U1") (pin "60") (pinfunction "AVDD_60") (pintype "bidirectional"))
    )
    (net (code "27") (name "Net-(U1-XTAL1)") (class "Default")
      (node (ref "C4") (pin "1") (pinfunction "1_1") (pintype "passive"))
      (node (ref "U1") (pin "57") (pinfunction "XTAL1_57") (pintype "bidirectional"))
      (node (ref "Y1") (pin "3") (pinfunction "2_3") (pintype "passive"))
    )
    (net (code "28") (name "Net-(U1-XTAL2)") (class "Default")
      (node (ref "C3") (pin "1") (pinfunction "1_1") (pintype "passive"))
      (node (ref "U1") (pin "56") (pinfunction "XTAL2_56") (pintype "bidirectional"))
      (node (ref "Y1") (pin "1") (pinfunction "1_1") (pintype "passive"))
    )
    (net (code "29") (name "PB6") (class "Default")
      (node (ref "R12") (pin "2") (pinfunction "2_2") (pintype "passive"))
      (node (ref "U1") (pin "42") (pinfunction "PB6(OC1B/PCINT6)_42") (pintype "bidirectional"))
    )
    (net (code "30") (name "PB7") (class "Default")
      (node (ref "R13") (pin "2") (pinfunction "2_2") (pintype "passive"))
      (node (ref "U1") (pin "43") (pinfunction "PB7(OC0A/OC1C/PCINT7)_43") (pintype "bidirectional"))
    )
    (net (code "31") (name "PWM1") (class "Default")
      (node (ref "J3") (pin "8") (pinfunction "8_8") (pintype "passive"))
      (node (ref "R4") (pin "1") (pinfunction "1_1") (pintype "passive"))
      (node (ref "U1") (pin "49") (pinfunction "PE3(OC3A/AIN1)_49") (pintype "bidirectional"))
    )
    (net (code "32") (name "PWM2") (class "Default")
      (node (ref "J3") (pin "4") (pinfunction "4_4") (pintype "passive"))
      (node (ref "R6") (pin "1") (pinfunction "1_1") (pintype "passive"))
      (node (ref "U1") (pin "50") (pinfunction "PE4(OC3B/INT4)_50") (pintype "bidirectional"))
    )
    (net (code "33") (name "PWM3") (class "Default")
      (node (ref "J3") (pin "7") (pinfunction "7_7") (pintype "passive"))
      (node (ref "R8") (pin "1") (pinfunction "1_1") (pintype "passive"))
      (node (ref "U1") (pin "51") (pinfunction "PE5(OC3C/INT5)_51") (pintype "bidirectional"))
    )
    (net (code "34") (name "PWM4") (class "Default")
      (node (ref "J3") (pin "3") (pinfunction "3_3") (pintype "passive"))
      (node (ref "R10") (pin "1") (pinfunction "1_1") (pintype "passive"))
      (node (ref "U1") (pin "41") (pinfunction "PB5(OC1A/PCINT5)_41") (pintype "bidirectional"))
    )
    (net (code "35") (name "RESET") (class "Default")
      (node (ref "C9") (pin "2") (pinfunction "2_2") (pintype "passive"))
      (node (ref "J1") (pin "5") (pinfunction "5_5") (pintype "passive"))
      (node (ref "R1") (pin "1") (pinfunction "1_1") (pintype "passive"))
      (node (ref "SW") (pin "1") (pinfunction "1_1") (pintype "passive"))
      (node (ref "SW") (pin "2") (pinfunction "1_2") (pintype "passive"))
      (node (ref "U1") (pin "12") (pinfunction "RSTN_12") (pintype "bidirectional"))
    )
    (net (code "36") (name "RXD0") (class "Default")
      (node (ref "JP1") (pin "TXO") (pinfunction "3_TXO") (pintype "passive"))
      (node (ref "U1") (pin "46") (pinfunction "PE0(RXD0/PCINT8)_46") (pintype "bidirectional"))
    )
    (net (code "37") (name "SCK") (class "Default")
      (node (ref "J1") (pin "3") (pinfunction "3_3") (pintype "passive"))
      (node (ref "U1") (pin "37") (pinfunction "PB1(SCK/PCINT1)_37") (pintype "bidirectional"))
    )
    (net (code "38") (name "SCL") (class "Default")
      (node (ref "J3") (pin "6") (pinfunction "6_6") (pintype "passive"))
      (node (ref "R3") (pin "1") (pinfunction "1_1") (pintype "passive"))
      (node (ref "U1") (pin "25") (pinfunction "PD0(SCL/INT0)_25") (pintype "bidirectional"))
      (node (ref "U2") (pin "SCL/SPC") (pinfunction "SCL/SPC_SCL/SPC") (pintype "bidirectional"))
    )
    (net (code "39") (name "SDA") (class "Default")
      (node (ref "J3") (pin "5") (pinfunction "5_5") (pintype "passive"))
      (node (ref "R2") (pin "1") (pinfunction "1_1") (pintype "passive"))
      (node (ref "U1") (pin "26") (pinfunction "PD1(SDA/INT1)_26") (pintype "bidirectional"))
      (node (ref "U2") (pin "SDA/SDI/SDO") (pinfunction "SDA/SDI/SDO_SDA/SDI/SDO") (pintype "bidirectional"))
    )
    (net (code "40") (name "TXD0") (class "Default")
      (node (ref "JP1") (pin "RXI") (pinfunction "2_RXI") (pintype "passive"))
      (node (ref "U1") (pin "47") (pinfunction "PE1(TXD0)_47") (pintype "bidirectional"))
    )
    (net (code "41") (name "VBAT") (class "Default")
      (node (ref "C15") (pin "1") (pinfunction "1_1") (pintype "passive"))
      (node (ref "C17") (pin "1") (pinfunction "+_1") (pintype "passive"))
      (node (ref "C18") (pin "1") (pinfunction "+_1") (pintype "passive"))
      (node (ref "C19") (pin "1") (pinfunction "+_1") (pintype "passive"))
      (node (ref "C20") (pin "1") (pinfunction "+_1") (pintype "passive"))
      (node (ref "D1") (pin "C") (pinfunction "C_C") (pintype "passive"))
      (node (ref "D2") (pin "C") (pinfunction "C_C") (pintype "passive"))
      (node (ref "D3") (pin "C") (pinfunction "C_C") (pintype "passive"))
      (node (ref "D4") (pin "C") (pinfunction "C_C") (pintype "passive"))
      (node (ref "J2") (pin "2") (pinfunction "2_2") (pintype "passive"))
      (node (ref "J3") (pin "9") (pinfunction "9_9") (pintype "passive"))
      (node (ref "M1") (pin "V+") (pinfunction "V+_V+") (pintype "bidirectional"))
      (node (ref "M2") (pin "V+") (pinfunction "V+_V+") (pintype "bidirectional"))
      (node (ref "M3") (pin "V+") (pinfunction "V+_V+") (pintype "bidirectional"))
      (node (ref "M4") (pin "V+") (pinfunction "V+_V+") (pintype "bidirectional"))
      (node (ref "R14") (pin "2") (pinfunction "2_2") (pintype "passive"))
      (node (ref "REG") (pin "1") (pinfunction "IN_1") (pintype "input"))
      (node (ref "REG") (pin "3") (pinfunction "EN_3") (pintype "input"))
      (node (ref "V10") (pin "P1") (pinfunction "N_P1") (pintype "bidirectional"))
      (node (ref "V11") (pin "P1") (pinfunction "N_P1") (pintype "bidirectional"))
      (node (ref "V12") (pin "P1") (pinfunction "N_P1") (pintype "bidirectional"))
      (node (ref "V9") (pin "P1") (pinfunction "N_P1") (pintype "bidirectional"))
    )
    (net (code "42") (name "unconnected-(J1-Pad2)") (class "Default")
      (node (ref "J1") (pin "2") (pinfunction "2_2") (pintype "passive"))
    )
    (net (code "43") (name "unconnected-(JP1-4-PadVCC)") (class "Default")
      (node (ref "JP1") (pin "VCC") (pinfunction "4_VCC") (pintype "passive"))
    )
    (net (code "44") (name "unconnected-(JP1-5-PadCTS)") (class "Default")
      (node (ref "JP1") (pin "CTS") (pinfunction "5_CTS") (pintype "passive"))
    )
    (net (code "45") (name "unconnected-(REG-NC{slash}FB-Pad4)") (class "Default")
      (node (ref "REG") (pin "4") (pinfunction "NC/FB_4") (pintype "passive"))
    )
    (net (code "46") (name "unconnected-(U1-AREF-Pad62)") (class "Default")
      (node (ref "U1") (pin "62") (pinfunction "AREF_62") (pintype "bidirectional"))
    )
    (net (code "47") (name "unconnected-(U1-PB0(SSN{slash}PCINT0)-Pad36)") (class "Default")
      (node (ref "U1") (pin "36") (pinfunction "PB0(SSN/PCINT0)_36") (pintype "bidirectional"))
    )
    (net (code "48") (name "unconnected-(U1-PB4(OC2A{slash}PCINT4)-Pad40)") (class "Default")
      (node (ref "U1") (pin "40") (pinfunction "PB4(OC2A/PCINT4)_40") (pintype "bidirectional"))
    )
    (net (code "49") (name "unconnected-(U1-PD2(RXD1{slash}INT2)-Pad27)") (class "Default")
      (node (ref "U1") (pin "27") (pinfunction "PD2(RXD1/INT2)_27") (pintype "bidirectional"))
    )
    (net (code "50") (name "unconnected-(U1-PD3(TXD1{slash}INT3)-Pad28)") (class "Default")
      (node (ref "U1") (pin "28") (pinfunction "PD3(TXD1/INT3)_28") (pintype "bidirectional"))
    )
    (net (code "51") (name "unconnected-(U1-PD4(ICP1)-Pad29)") (class "Default")
      (node (ref "U1") (pin "29") (pinfunction "PD4(ICP1)_29") (pintype "bidirectional"))
    )
    (net (code "52") (name "unconnected-(U1-PD5(XCK1)-Pad30)") (class "Default")
      (node (ref "U1") (pin "30") (pinfunction "PD5(XCK1)_30") (pintype "bidirectional"))
    )
    (net (code "53") (name "unconnected-(U1-PD6(T1)-Pad31)") (class "Default")
      (node (ref "U1") (pin "31") (pinfunction "PD6(T1)_31") (pintype "bidirectional"))
    )
    (net (code "54") (name "unconnected-(U1-PD7(T0)-Pad32)") (class "Default")
      (node (ref "U1") (pin "32") (pinfunction "PD7(T0)_32") (pintype "bidirectional"))
    )
    (net (code "55") (name "unconnected-(U1-PE2(XCK0{slash}AIN0)-Pad48)") (class "Default")
      (node (ref "U1") (pin "48") (pinfunction "PE2(XCK0/AIN0)_48") (pintype "bidirectional"))
    )
    (net (code "56") (name "unconnected-(U1-PE6(T3{slash}INT6)-Pad52)") (class "Default")
      (node (ref "U1") (pin "52") (pinfunction "PE6(T3/INT6)_52") (pintype "bidirectional"))
    )
    (net (code "57") (name "unconnected-(U1-PE7(ICP3{slash}INT7{slash}CLKO)-Pad53)") (class "Default")
      (node (ref "U1") (pin "53") (pinfunction "PE7(ICP3/INT7/CLKO)_53") (pintype "bidirectional"))
    )
    (net (code "58") (name "unconnected-(U1-PF0(ADC0)-Pad63)") (class "Default")
      (node (ref "U1") (pin "63") (pinfunction "PF0(ADC0)_63") (pintype "bidirectional"))
    )
    (net (code "59") (name "unconnected-(U1-PF1(ADC1)-Pad64)") (class "Default")
      (node (ref "U1") (pin "64") (pinfunction "PF1(ADC1)_64") (pintype "bidirectional"))
    )
    (net (code "60") (name "unconnected-(U1-PF2(ADC2{slash}DIG2)-Pad1)") (class "Default")
      (node (ref "U1") (pin "1") (pinfunction "PF2(ADC2/DIG2)_1") (pintype "bidirectional"))
    )
    (net (code "61") (name "unconnected-(U1-PF3(ADC3{slash}DIG4)-Pad2)") (class "Default")
      (node (ref "U1") (pin "2") (pinfunction "PF3(ADC3/DIG4)_2") (pintype "bidirectional"))
    )
    (net (code "62") (name "unconnected-(U1-PF4(ADC4{slash}TCK)-Pad3)") (class "Default")
      (node (ref "U1") (pin "3") (pinfunction "PF4(ADC4/TCK)_3") (pintype "bidirectional"))
    )
    (net (code "63") (name "unconnected-(U1-PF5(ADC5{slash}TMS)-Pad4)") (class "Default")
      (node (ref "U1") (pin "4") (pinfunction "PF5(ADC5/TMS)_4") (pintype "bidirectional"))
    )
    (net (code "64") (name "unconnected-(U1-PF6(ADC6{slash}TDO)-Pad5)") (class "Default")
      (node (ref "U1") (pin "5") (pinfunction "PF6(ADC6/TDO)_5") (pintype "bidirectional"))
    )
    (net (code "65") (name "unconnected-(U1-PF7(ADC7{slash}TDI)-Pad6)") (class "Default")
      (node (ref "U1") (pin "6") (pinfunction "PF7(ADC7/TDI)_6") (pintype "bidirectional"))
    )
    (net (code "66") (name "unconnected-(U1-PG0(DIG3)-Pad14)") (class "Default")
      (node (ref "U1") (pin "14") (pinfunction "PG0(DIG3)_14") (pintype "bidirectional"))
    )
    (net (code "67") (name "unconnected-(U1-PG1(DIG1)-Pad15)") (class "Default")
      (node (ref "U1") (pin "15") (pinfunction "PG1(DIG1)_15") (pintype "bidirectional"))
    )
    (net (code "68") (name "unconnected-(U1-PG2(AMR)-Pad16)") (class "Default")
      (node (ref "U1") (pin "16") (pinfunction "PG2(AMR)_16") (pintype "bidirectional"))
    )
    (net (code "69") (name "unconnected-(U1-PG3(TOSC2)-Pad17)") (class "Default")
      (node (ref "U1") (pin "17") (pinfunction "PG3(TOSC2)_17") (pintype "bidirectional"))
    )
    (net (code "70") (name "unconnected-(U1-PG4(TOSC1)-Pad18)") (class "Default")
      (node (ref "U1") (pin "18") (pinfunction "PG4(TOSC1)_18") (pintype "bidirectional"))
    )
    (net (code "71") (name "unconnected-(U1-PG5(OC0B)-Pad19)") (class "Default")
      (node (ref "U1") (pin "19") (pinfunction "PG5(OC0B)_19") (pintype "bidirectional"))
    )
    (net (code "72") (name "unconnected-(U1-RSTON-Pad13)") (class "Default")
      (node (ref "U1") (pin "13") (pinfunction "RSTON_13") (pintype "bidirectional"))
    )
    (net (code "73") (name "unconnected-(U2-PadDRDY_M)") (class "Default")
      (node (ref "U2") (pin "DRDY_M") (pinfunction "DRDY_M_DRDY_M") (pintype "bidirectional"))
    )
    (net (code "74") (name "unconnected-(U2-PadINT1_A{slash}G)") (class "Default")
      (node (ref "U2") (pin "INT1_A/G") (pinfunction "INT1_A/G_INT1_A/G") (pintype "bidirectional"))
    )
    (net (code "75") (name "unconnected-(U2-PadINT2_A{slash}G)") (class "Default")
      (node (ref "U2") (pin "INT2_A/G") (pinfunction "INT2_A/G_INT2_A/G") (pintype "bidirectional"))
    )
    (net (code "76") (name "unconnected-(U2-PadINT_M)") (class "Default")
      (node (ref "U2") (pin "INT_M") (pinfunction "INT_M_INT_M") (pintype "bidirectional"))
    )
  )
)
